# SubBus9.net
KiCad netlist of a schematic drawn in Altium Designer
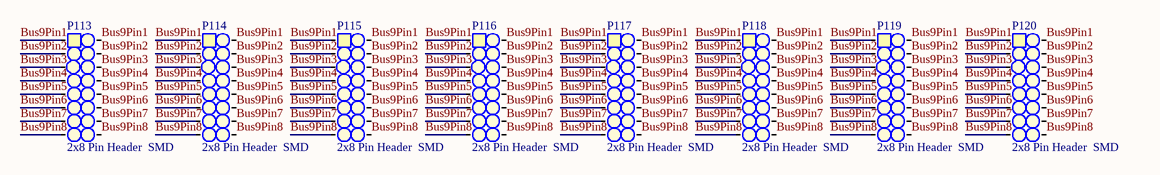
[diagram p0: SubBus9.SchDoc]

(export (version "E")
  (design (tool "Eeschema 10.0.6"))
  (components
    (comp (ref "P113")
      (value "2x8 Pin Header  SMD")
      (footprint "2X8_SMD_PH_2.54")
      (description "2.54mm, SMD")
      (libsource (lib "jclib") (part "2x8 Pin Header  SMD"))
    )
    (comp (ref "P114")
      (value "2x8 Pin Header  SMD")
      (footprint "2X8_SMD_PH_2.54")
      (description "2.54mm, SMD")
      (libsource (lib "jclib") (part "2x8 Pin Header  SMD"))
    )
    (comp (ref "P115")
      (value "2x8 Pin Header  SMD")
      (footprint "2X8_SMD_PH_2.54")
      (description "2.54mm, SMD")
      (libsource (lib "jclib") (part "2x8 Pin Header  SMD"))
    )
    (comp (ref "P116")
      (value "2x8 Pin Header  SMD")
      (footprint "2X8_SMD_PH_2.54")
      (description "2.54mm, SMD")
      (libsource (lib "jclib") (part "2x8 Pin Header  SMD"))
    )
    (comp (ref "P117")
      (value "2x8 Pin Header  SMD")
      (footprint "2X8_SMD_PH_2.54")
      (description "2.54mm, SMD")
      (libsource (lib "jclib") (part "2x8 Pin Header  SMD"))
    )
    (comp (ref "P118")
      (value "2x8 Pin Header  SMD")
      (footprint "2X8_SMD_PH_2.54")
      (description "2.54mm, SMD")
      (libsource (lib "jclib") (part "2x8 Pin Header  SMD"))
    )
    (comp (ref "P119")
      (value "2x8 Pin Header  SMD")
      (footprint "2X8_SMD_PH_2.54")
      (description "2.54mm, SMD")
      (libsource (lib "jclib") (part "2x8 Pin Header  SMD"))
    )
    (comp (ref "P120")
      (value "2x8 Pin Header  SMD")
      (footprint "2X8_SMD_PH_2.54")
      (description "2.54mm, SMD")
      (libsource (lib "jclib") (part "2x8 Pin Header  SMD"))
    )
  )
  (nets
    (net (code "1") (name "/Bus9Pin1") (class "Default")
      (node (ref "P113") (pin "1") (pinfunction "1_1") (pintype "passive"))
      (node (ref "P113") (pin "16") (pinfunction "16_16") (pintype "passive"))
      (node (ref "P114") (pin "1") (pinfunction "1_1") (pintype "passive"))
      (node (ref "P114") (pin "16") (pinfunction "16_16") (pintype "passive"))
      (node (ref "P115") (pin "1") (pinfunction "1_1") (pintype "passive"))
      (node (ref "P115") (pin "16") (pinfunction "16_16") (pintype "passive"))
      (node (ref "P116") (pin "1") (pinfunction "1_1") (pintype "passive"))
      (node (ref "P116") (pin "16") (pinfunction "16_16") (pintype "passive"))
      (node (ref "P117") (pin "1") (pinfunction "1_1") (pintype "passive"))
      (node (ref "P117") (pin "16") (pinfunction "16_16") (pintype "passive"))
      (node (ref "P118") (pin "1") (pinfunction "1_1") (pintype "passive"))
      (node (ref "P118") (pin "16") (pinfunction "16_16") (pintype "passive"))
      (node (ref "P119") (pin "1") (pinfunction "1_1") (pintype "passive"))
      (node (ref "P119") (pin "16") (pinfunction "16_16") (pintype "passive"))
      (node (ref "P120") (pin "1") (pinfunction "1_1") (pintype "passive"))
      (node (ref "P120") (pin "16") (pinfunction "16_16") (pintype "passive"))
    )
    (net (code "2") (name "/Bus9Pin2") (class "Default")
      (node (ref "P113") (pin "15") (pinfunction "15_15") (pintype "passive"))
      (node (ref "P113") (pin "2") (pinfunction "2_2") (pintype "passive"))
      (node (ref "P114") (pin "15") (pinfunction "15_15") (pintype "passive"))
      (node (ref "P114") (pin "2") (pinfunction "2_2") (pintype "passive"))
      (node (ref "P115") (pin "15") (pinfunction "15_15") (pintype "passive"))
      (node (ref "P115") (pin "2") (pinfunction "2_2") (pintype "passive"))
      (node (ref "P116") (pin "15") (pinfunction "15_15") (pintype "passive"))
      (node (ref "P116") (pin "2") (pinfunction "2_2") (pintype "passive"))
      (node (ref "P117") (pin "15") (pinfunction "15_15") (pintype "passive"))
      (node (ref "P117") (pin "2") (pinfunction "2_2") (pintype "passive"))
      (node (ref "P118") (pin "15") (pinfunction "15_15") (pintype "passive"))
      (node (ref "P118") (pin "2") (pinfunction "2_2") (pintype "passive"))
      (node (ref "P119") (pin "15") (pinfunction "15_15") (pintype "passive"))
      (node (ref "P119") (pin "2") (pinfunction "2_2") (pintype "passive"))
      (node (ref "P120") (pin "15") (pinfunction "15_15") (pintype "passive"))
      (node (ref "P120") (pin "2") (pinfunction "2_2") (pintype "passive"))
    )
    (net (code "3") (name "/Bus9Pin3") (class "Default")
      (node (ref "P113") (pin "14") (pinfunction "14_14") (pintype "passive"))
      (node (ref "P113") (pin "3") (pinfunction "3_3") (pintype "passive"))
      (node (ref "P114") (pin "14") (pinfunction "14_14") (pintype "passive"))
      (node (ref "P114") (pin "3") (pinfunction "3_3") (pintype "passive"))
      (node (ref "P115") (pin "14") (pinfunction "14_14") (pintype "passive"))
      (node (ref "P115") (pin "3") (pinfunction "3_3") (pintype "passive"))
      (node (ref "P116") (pin "14") (pinfunction "14_14") (pintype "passive"))
      (node (ref "P116") (pin "3") (pinfunction "3_3") (pintype "passive"))
      (node (ref "P117") (pin "14") (pinfunction "14_14") (pintype "passive"))
      (node (ref "P117") (pin "3") (pinfunction "3_3") (pintype "passive"))
      (node (ref "P118") (pin "14") (pinfunction "14_14") (pintype "passive"))
      (node (ref "P118") (pin "3") (pinfunction "3_3") (pintype "passive"))
      (node (ref "P119") (pin "14") (pinfunction "14_14") (pintype "passive"))
      (node (ref "P119") (pin "3") (pinfunction "3_3") (pintype "passive"))
      (node (ref "P120") (pin "14") (pinfunction "14_14") (pintype "passive"))
      (node (ref "P120") (pin "3") (pinfunction "3_3") (pintype "passive"))
    )
    (net (code "4") (name "/Bus9Pin4") (class "Default")
      (node (ref "P113") (pin "13") (pinfunction "13_13") (pintype "passive"))
      (node (ref "P113") (pin "4") (pinfunction "4_4") (pintype "passive"))
      (node (ref "P114") (pin "13") (pinfunction "13_13") (pintype "passive"))
      (node (ref "P114") (pin "4") (pinfunction "4_4") (pintype "passive"))
      (node (ref "P115") (pin "13") (pinfunction "13_13") (pintype "passive"))
      (node (ref "P115") (pin "4") (pinfunction "4_4") (pintype "passive"))
      (node (ref "P116") (pin "13") (pinfunction "13_13") (pintype "passive"))
      (node (ref "P116") (pin "4") (pinfunction "4_4") (pintype "passive"))
      (node (ref "P117") (pin "13") (pinfunction "13_13") (pintype "passive"))
      (node (ref "P117") (pin "4") (pinfunction "4_4") (pintype "passive"))
      (node (ref "P118") (pin "13") (pinfunction "13_13") (pintype "passive"))
      (node (ref "P118") (pin "4") (pinfunction "4_4") (pintype "passive"))
      (node (ref "P119") (pin "13") (pinfunction "13_13") (pintype "passive"))
      (node (ref "P119") (pin "4") (pinfunction "4_4") (pintype "passive"))
      (node (ref "P120") (pin "13") (pinfunction "13_13") (pintype "passive"))
      (node (ref "P120") (pin "4") (pinfunction "4_4") (pintype "passive"))
    )
    (net (code "5") (name "/Bus9Pin5") (class "Default")
      (node (ref "P113") (pin "12") (pinfunction "12_12") (pintype "passive"))
      (node (ref "P113") (pin "5") (pinfunction "5_5") (pintype "passive"))
      (node (ref "P114") (pin "12") (pinfunction "12_12") (pintype "passive"))
      (node (ref "P114") (pin "5") (pinfunction "5_5") (pintype "passive"))
      (node (ref "P115") (pin "12") (pinfunction "12_12") (pintype "passive"))
      (node (ref "P115") (pin "5") (pinfunction "5_5") (pintype "passive"))
      (node (ref "P116") (pin "12") (pinfunction "12_12") (pintype "passive"))
      (node (ref "P116") (pin "5") (pinfunction "5_5") (pintype "passive"))
      (node (ref "P117") (pin "12") (pinfunction "12_12") (pintype "passive"))
      (node (ref "P117") (pin "5") (pinfunction "5_5") (pintype "passive"))
      (node (ref "P118") (pin "12") (pinfunction "12_12") (pintype "passive"))
      (node (ref "P118") (pin "5") (pinfunction "5_5") (pintype "passive"))
      (node (ref "P119") (pin "12") (pinfunction "12_12") (pintype "passive"))
      (node (ref "P119") (pin "5") (pinfunction "5_5") (pintype "passive"))
      (node (ref "P120") (pin "12") (pinfunction "12_12") (pintype "passive"))
      (node (ref "P120") (pin "5") (pinfunction "5_5") (pintype "passive"))
    )
    (net (code "6") (name "/Bus9Pin6") (class "Default")
      (node (ref "P113") (pin "11") (pinfunction "11_11") (pintype "passive"))
      (node (ref "P113") (pin "6") (pinfunction "6_6") (pintype "passive"))
      (node (ref "P114") (pin "11") (pinfunction "11_11") (pintype "passive"))
      (node (ref "P114") (pin "6") (pinfunction "6_6") (pintype "passive"))
      (node (ref "P115") (pin "11") (pinfunction "11_11") (pintype "passive"))
      (node (ref "P115") (pin "6") (pinfunction "6_6") (pintype "passive"))
      (node (ref "P116") (pin "11") (pinfunction "11_11") (pintype "passive"))
      (node (ref "P116") (pin "6") (pinfunction "6_6") (pintype "passive"))
      (node (ref "P117") (pin "11") (pinfunction "11_11") (pintype "passive"))
      (node (ref "P117") (pin "6") (pinfunction "6_6") (pintype "passive"))
      (node (ref "P118") (pin "11") (pinfunction "11_11") (pintype "passive"))
      (node (ref "P118") (pin "6") (pinfunction "6_6") (pintype "passive"))
      (node (ref "P119") (pin "11") (pinfunction "11_11") (pintype "passive"))
      (node (ref "P119") (pin "6") (pinfunction "6_6") (pintype "passive"))
      (node (ref "P120") (pin "11") (pinfunction "11_11") (pintype "passive"))
      (node (ref "P120") (pin "6") (pinfunction "6_6") (pintype "passive"))
    )
    (net (code "7") (name "/Bus9Pin7") (class "Default")
      (node (ref "P113") (pin "10") (pinfunction "10_10") (pintype "passive"))
      (node (ref "P113") (pin "7") (pinfunction "7_7") (pintype "passive"))
      (node (ref "P114") (pin "10") (pinfunction "10_10") (pintype "passive"))
      (node (ref "P114") (pin "7") (pinfunction "7_7") (pintype "passive"))
      (node (ref "P115") (pin "10") (pinfunction "10_10") (pintype "passive"))
      (node (ref "P115") (pin "7") (pinfunction "7_7") (pintype "passive"))
      (node (ref "P116") (pin "10") (pinfunction "10_10") (pintype "passive"))
      (node (ref "P116") (pin "7") (pinfunction "7_7") (pintype "passive"))
      (node (ref "P117") (pin "10") (pinfunction "10_10") (pintype "passive"))
      (node (ref "P117") (pin "7") (pinfunction "7_7") (pintype "passive"))
      (node (ref "P118") (pin "10") (pinfunction "10_10") (pintype "passive"))
      (node (ref "P118") (pin "7") (pinfunction "7_7") (pintype "passive"))
      (node (ref "P119") (pin "10") (pinfunction "10_10") (pintype "passive"))
      (node (ref "P119") (pin "7") (pinfunction "7_7") (pintype "passive"))
      (node (ref "P120") (pin "10") (pinfunction "10_10") (pintype "passive"))
      (node (ref "P120") (pin "7") (pinfunction "7_7") (pintype "passive"))
    )
    (net (code "8") (name "/Bus9Pin8") (class "Default")
      (node (ref "P113") (pin "8") (pinfunction "8_8") (pintype "passive"))
      (node (ref "P113") (pin "9") (pinfunction "9_9") (pintype "passive"))
      (node (ref "P114") (pin "8") (pinfunction "8_8") (pintype "passive"))
      (node (ref "P114") (pin "9") (pinfunction "9_9") (pintype "passive"))
      (node (ref "P115") (pin "8") (pinfunction "8_8") (pintype "passive"))
      (node (ref "P115") (pin "9") (pinfunction "9_9") (pintype "passive"))
      (node (ref "P116") (pin "8") (pinfunction "8_8") (pintype "passive"))
      (node (ref "P116") (pin "9") (pinfunction "9_9") (pintype "passive"))
      (node (ref "P117") (pin "8") (pinfunction "8_8") (pintype "passive"))
      (node (ref "P117") (pin "9") (pinfunction "9_9") (pintype "passive"))
      (node (ref "P118") (pin "8") (pinfunction "8_8") (pintype "passive"))
      (node (ref "P118") (pin "9") (pinfunction "9_9") (pintype "passive"))
      (node (ref "P119") (pin "8") (pinfunction "8_8") (pintype "passive"))
      (node (ref "P119") (pin "9") (pinfunction "9_9") (pintype "passive"))
      (node (ref "P120") (pin "8") (pinfunction "8_8") (pintype "passive"))
      (node (ref "P120") (pin "9") (pinfunction "9_9") (pintype "passive"))
    )
  )
)
